# CapstoneREV_10-5-25_1.net
KiCad netlist of a schematic drawn in EAGLE
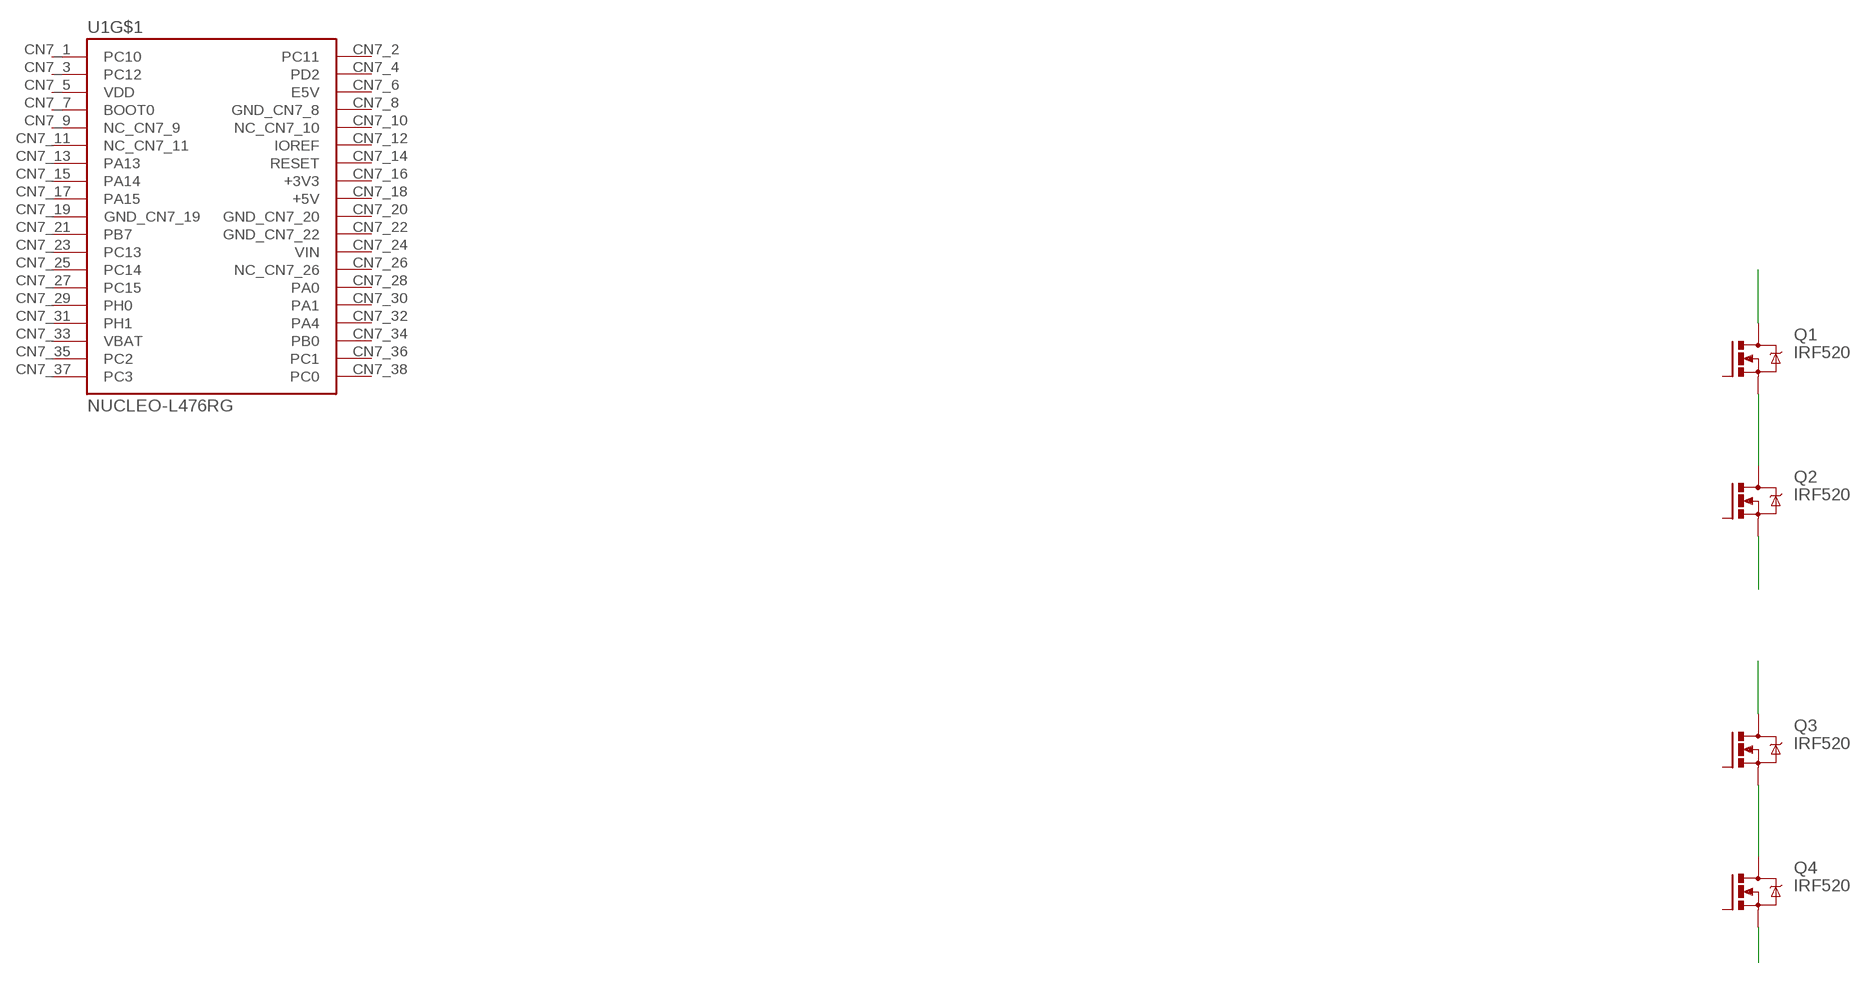
[diagram p0: schematic, sheet 1]

(export (version "E")
  (design (tool "Eeschema 10.0.6"))
  (components
    (comp (ref "Q1")
      (value "IRF520")
      (footprint "eagle-import:TO220BV")
      (libsource (lib "eagle-import") (part "IRF520"))
    )
    (comp (ref "Q2")
      (value "IRF520")
      (footprint "eagle-import:TO220BV")
      (libsource (lib "eagle-import") (part "IRF520"))
    )
    (comp (ref "Q3")
      (value "IRF520")
      (footprint "eagle-import:TO220BV")
      (libsource (lib "eagle-import") (part "IRF520"))
    )
    (comp (ref "Q4")
      (value "IRF520")
      (footprint "eagle-import:TO220BV")
      (libsource (lib "eagle-import") (part "IRF520"))
    )
    (comp (ref "U1")
      (value "NUCLEO-L476RG")
      (footprint "eagle-import:MODULE_NUCLEO-L476RG")
      (fields (field (name "MANUFACTURER") "STmicroelectronics"))
      (libsource (lib "eagle-import") (part "NUCLEO-L476RG"))
    )
  )
  (nets
    (net (code "1") (name "/+3V3") (class "Default")
      (node (ref "U1") (pin "CN7_16") (pinfunction "+3V3_CN7_16") (pintype "power_in"))
    )
    (net (code "2") (name "/+5V") (class "Default")
      (node (ref "U1") (pin "CN7_18") (pinfunction "+5V_CN7_18") (pintype "power_in"))
    )
    (net (code "3") (name "/E5V") (class "Default")
      (node (ref "U1") (pin "CN7_6") (pinfunction "E5V_CN7_6") (pintype "power_in"))
    )
    (net (code "4") (name "/GND_CN7_8") (class "Default")
      (node (ref "U1") (pin "CN7_8") (pinfunction "GND_CN7_8_CN7_8") (pintype "power_in"))
    )
    (net (code "5") (name "/GND_CN7_19") (class "Default")
      (node (ref "U1") (pin "CN7_19") (pinfunction "GND_CN7_19_CN7_19") (pintype "power_in"))
    )
    (net (code "6") (name "/GND_CN7_20") (class "Default")
      (node (ref "U1") (pin "CN7_20") (pinfunction "GND_CN7_20_CN7_20") (pintype "power_in"))
    )
    (net (code "7") (name "/GND_CN7_22") (class "Default")
      (node (ref "U1") (pin "CN7_22") (pinfunction "GND_CN7_22_CN7_22") (pintype "power_in"))
    )
    (net (code "8") (name "/VBAT") (class "Default")
      (node (ref "U1") (pin "CN7_33") (pinfunction "VBAT_CN7_33") (pintype "power_in"))
    )
    (net (code "9") (name "/VDD") (class "Default")
      (node (ref "U1") (pin "CN7_5") (pinfunction "VDD_CN7_5") (pintype "power_in"))
    )
    (net (code "10") (name "/VIN") (class "Default")
      (node (ref "U1") (pin "CN7_24") (pinfunction "VIN_CN7_24") (pintype "power_in"))
    )
    (net (code "11") (name "Net-(Q1-PadS)") (class "Default")
      (node (ref "Q1") (pin "S") (pinfunction "S_S") (pintype "passive"))
      (node (ref "Q2") (pin "D") (pinfunction "D_D") (pintype "passive"))
    )
    (net (code "12") (name "Net-(Q3-PadS)") (class "Default")
      (node (ref "Q3") (pin "S") (pinfunction "S_S") (pintype "passive"))
      (node (ref "Q4") (pin "D") (pinfunction "D_D") (pintype "passive"))
    )
    (net (code "13") (name "unconnected-(Q1-PadD)") (class "Default")
      (node (ref "Q1") (pin "D") (pinfunction "D_D") (pintype "passive"))
    )
    (net (code "14") (name "unconnected-(Q1-PadG)") (class "Default")
      (node (ref "Q1") (pin "G") (pinfunction "G_G") (pintype "passive"))
    )
    (net (code "15") (name "unconnected-(Q2-PadG)") (class "Default")
      (node (ref "Q2") (pin "G") (pinfunction "G_G") (pintype "passive"))
    )
    (net (code "16") (name "unconnected-(Q2-PadS)") (class "Default")
      (node (ref "Q2") (pin "S") (pinfunction "S_S") (pintype "passive"))
    )
    (net (code "17") (name "unconnected-(Q3-PadD)") (class "Default")
      (node (ref "Q3") (pin "D") (pinfunction "D_D") (pintype "passive"))
    )
    (net (code "18") (name "unconnected-(Q3-PadG)") (class "Default")
      (node (ref "Q3") (pin "G") (pinfunction "G_G") (pintype "passive"))
    )
    (net (code "19") (name "unconnected-(Q4-PadG)") (class "Default")
      (node (ref "Q4") (pin "G") (pinfunction "G_G") (pintype "passive"))
    )
    (net (code "20") (name "unconnected-(Q4-PadS)") (class "Default")
      (node (ref "Q4") (pin "S") (pinfunction "S_S") (pintype "passive"))
    )
    (net (code "21") (name "unconnected-(U1A-BOOT0-PadCN7_7)") (class "Default")
      (node (ref "U1") (pin "CN7_7") (pinfunction "BOOT0_CN7_7") (pintype "input"))
    )
    (net (code "22") (name "unconnected-(U1A-IOREF-PadCN7_12)") (class "Default")
      (node (ref "U1") (pin "CN7_12") (pinfunction "IOREF_CN7_12") (pintype "input"))
    )
    (net (code "23") (name "unconnected-(U1A-NC_CN7_9-PadCN7_9)") (class "Default")
      (node (ref "U1") (pin "CN7_9") (pinfunction "NC_CN7_9_CN7_9") (pintype "no_connect"))
    )
    (net (code "24") (name "unconnected-(U1A-NC_CN7_10-PadCN7_10)") (class "Default")
      (node (ref "U1") (pin "CN7_10") (pinfunction "NC_CN7_10_CN7_10") (pintype "no_connect"))
    )
    (net (code "25") (name "unconnected-(U1A-NC_CN7_11-PadCN7_11)") (class "Default")
      (node (ref "U1") (pin "CN7_11") (pinfunction "NC_CN7_11_CN7_11") (pintype "no_connect"))
    )
    (net (code "26") (name "unconnected-(U1A-NC_CN7_26-PadCN7_26)") (class "Default")
      (node (ref "U1") (pin "CN7_26") (pinfunction "NC_CN7_26_CN7_26") (pintype "no_connect"))
    )
    (net (code "27") (name "unconnected-(U1A-PA0-PadCN7_28)") (class "Default")
      (node (ref "U1") (pin "CN7_28") (pinfunction "PA0_CN7_28") (pintype "bidirectional"))
    )
    (net (code "28") (name "unconnected-(U1A-PA1-PadCN7_30)") (class "Default")
      (node (ref "U1") (pin "CN7_30") (pinfunction "PA1_CN7_30") (pintype "bidirectional"))
    )
    (net (code "29") (name "unconnected-(U1A-PA4-PadCN7_32)") (class "Default")
      (node (ref "U1") (pin "CN7_32") (pinfunction "PA4_CN7_32") (pintype "bidirectional"))
    )
    (net (code "30") (name "unconnected-(U1A-PA13-PadCN7_13)") (class "Default")
      (node (ref "U1") (pin "CN7_13") (pinfunction "PA13_CN7_13") (pintype "bidirectional"))
    )
    (net (code "31") (name "unconnected-(U1A-PA14-PadCN7_15)") (class "Default")
      (node (ref "U1") (pin "CN7_15") (pinfunction "PA14_CN7_15") (pintype "bidirectional"))
    )
    (net (code "32") (name "unconnected-(U1A-PA15-PadCN7_17)") (class "Default")
      (node (ref "U1") (pin "CN7_17") (pinfunction "PA15_CN7_17") (pintype "bidirectional"))
    )
    (net (code "33") (name "unconnected-(U1A-PB0-PadCN7_34)") (class "Default")
      (node (ref "U1") (pin "CN7_34") (pinfunction "PB0_CN7_34") (pintype "bidirectional"))
    )
    (net (code "34") (name "unconnected-(U1A-PB7-PadCN7_21)") (class "Default")
      (node (ref "U1") (pin "CN7_21") (pinfunction "PB7_CN7_21") (pintype "bidirectional"))
    )
    (net (code "35") (name "unconnected-(U1A-PC0-PadCN7_38)") (class "Default")
      (node (ref "U1") (pin "CN7_38") (pinfunction "PC0_CN7_38") (pintype "bidirectional"))
    )
    (net (code "36") (name "unconnected-(U1A-PC1-PadCN7_36)") (class "Default")
      (node (ref "U1") (pin "CN7_36") (pinfunction "PC1_CN7_36") (pintype "bidirectional"))
    )
    (net (code "37") (name "unconnected-(U1A-PC2-PadCN7_35)") (class "Default")
      (node (ref "U1") (pin "CN7_35") (pinfunction "PC2_CN7_35") (pintype "bidirectional"))
    )
    (net (code "38") (name "unconnected-(U1A-PC3-PadCN7_37)") (class "Default")
      (node (ref "U1") (pin "CN7_37") (pinfunction "PC3_CN7_37") (pintype "bidirectional"))
    )
    (net (code "39") (name "unconnected-(U1A-PC10-PadCN7_1)") (class "Default")
      (node (ref "U1") (pin "CN7_1") (pinfunction "PC10_CN7_1") (pintype "bidirectional"))
    )
    (net (code "40") (name "unconnected-(U1A-PC11-PadCN7_2)") (class "Default")
      (node (ref "U1") (pin "CN7_2") (pinfunction "PC11_CN7_2") (pintype "bidirectional"))
    )
    (net (code "41") (name "unconnected-(U1A-PC12-PadCN7_3)") (class "Default")
      (node (ref "U1") (pin "CN7_3") (pinfunction "PC12_CN7_3") (pintype "bidirectional"))
    )
    (net (code "42") (name "unconnected-(U1A-PC13-PadCN7_23)") (class "Default")
      (node (ref "U1") (pin "CN7_23") (pinfunction "PC13_CN7_23") (pintype "bidirectional"))
    )
    (net (code "43") (name "unconnected-(U1A-PC14-PadCN7_25)") (class "Default")
      (node (ref "U1") (pin "CN7_25") (pinfunction "PC14_CN7_25") (pintype "bidirectional"))
    )
    (net (code "44") (name "unconnected-(U1A-PC15-PadCN7_27)") (class "Default")
      (node (ref "U1") (pin "CN7_27") (pinfunction "PC15_CN7_27") (pintype "bidirectional"))
    )
    (net (code "45") (name "unconnected-(U1A-PD2-PadCN7_4)") (class "Default")
      (node (ref "U1") (pin "CN7_4") (pinfunction "PD2_CN7_4") (pintype "bidirectional"))
    )
    (net (code "46") (name "unconnected-(U1A-PH0-PadCN7_29)") (class "Default")
      (node (ref "U1") (pin "CN7_29") (pinfunction "PH0_CN7_29") (pintype "bidirectional"))
    )
    (net (code "47") (name "unconnected-(U1A-PH1-PadCN7_31)") (class "Default")
      (node (ref "U1") (pin "CN7_31") (pinfunction "PH1_CN7_31") (pintype "bidirectional"))
    )
    (net (code "48") (name "unconnected-(U1A-RESET-PadCN7_14)") (class "Default")
      (node (ref "U1") (pin "CN7_14") (pinfunction "RESET_CN7_14") (pintype "input"))
    )
  )
)
